# BrauV2_GPIOExpander.net
KiCad netlist of a schematic drawn in Altium Designer
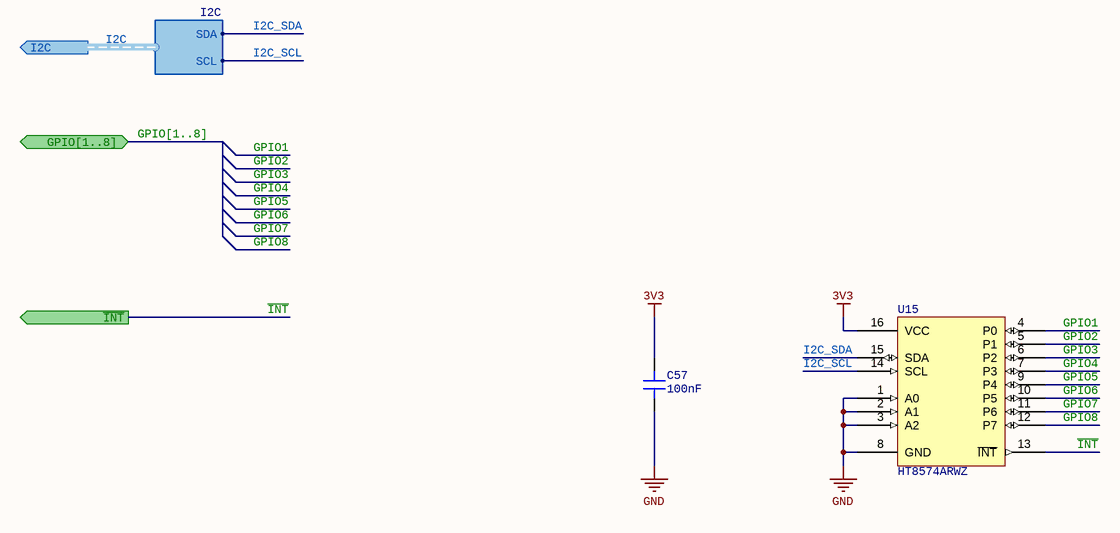
[diagram p0: BrauV2_GPIOExpander.SchDoc]

(export (version "E")
  (design (tool "Eeschema 10.0.6"))
  (components
    (comp (ref "C57")
      (value "CC0402KRX5R6BB104")
      (footprint "SMD_CAP_0402(1005)_N")
      (description "100nF ±10% 10V X5R 0402 Multilayer Ceramic Capacitors MLCC - SMD/SMT RoHS")
      (fields (field (name "TOLERANCE") "10%") (field (name "CAPACITANCE") "100nF"))
      (libsource (lib "BrauV2_Capacitor") (part "100nF 0402 10V 10%"))
    )
    (comp (ref "U15")
      (value "HT8574ARWZ")
      (footprint "TSSOP-16")
      (description "SOP16 Interface - I/O Expanders ROHS (PCF8754 clone)")
      (libsource (lib "BrauV2_IC") (part "HT8574ARWZ"))
    )
  )
  (nets
    (net (code "2") (name "/GPIO1") (class "Default")
      (node (ref "U15") (pin "4") (pinfunction "P0_4") (pintype "bidirectional"))
    )
    (net (code "3") (name "/GPIO2") (class "Default")
      (node (ref "U15") (pin "5") (pinfunction "P1_5") (pintype "bidirectional"))
    )
    (net (code "4") (name "/GPIO3") (class "Default")
      (node (ref "U15") (pin "6") (pinfunction "P2_6") (pintype "bidirectional"))
    )
    (net (code "5") (name "/GPIO4") (class "Default")
      (node (ref "U15") (pin "7") (pinfunction "P3_7") (pintype "bidirectional"))
    )
    (net (code "6") (name "/GPIO5") (class "Default")
      (node (ref "U15") (pin "9") (pinfunction "P4_9") (pintype "bidirectional"))
    )
    (net (code "7") (name "/GPIO6") (class "Default")
      (node (ref "U15") (pin "10") (pinfunction "P5_10") (pintype "bidirectional"))
    )
    (net (code "8") (name "/GPIO7") (class "Default")
      (node (ref "U15") (pin "11") (pinfunction "P6_11") (pintype "bidirectional"))
    )
    (net (code "9") (name "/GPIO8") (class "Default")
      (node (ref "U15") (pin "12") (pinfunction "P7_12") (pintype "bidirectional"))
    )
    (net (code "11") (name "/I2C_SCL") (class "Default")
      (node (ref "U15") (pin "14") (pinfunction "SCL_14") (pintype "input"))
    )
    (net (code "12") (name "/I2C_SDA") (class "Default")
      (node (ref "U15") (pin "15") (pinfunction "SDA_15") (pintype "bidirectional"))
    )
    (net (code "14") (name "/~{INT}") (class "Default")
      (node (ref "U15") (pin "13") (pinfunction "~{INT}_13") (pintype "output"))
    )
    (net (code "15") (name "3V3") (class "Default")
      (node (ref "C57") (pin "2") (pinfunction "2_2") (pintype "passive"))
      (node (ref "U15") (pin "16") (pinfunction "VCC_16") (pintype "power_in"))
    )
    (net (code "16") (name "GND") (class "Default")
      (node (ref "C57") (pin "1") (pinfunction "1_1") (pintype "passive"))
      (node (ref "U15") (pin "1") (pinfunction "A0_1") (pintype "input"))
      (node (ref "U15") (pin "2") (pinfunction "A1_2") (pintype "input"))
      (node (ref "U15") (pin "3") (pinfunction "A2_3") (pintype "input"))
      (node (ref "U15") (pin "8") (pinfunction "GND_8") (pintype "power_in"))
    )
  )
)
